# D1_2020-10-05_14-30-49.net
KiCad netlist of a schematic drawn in EasyEDA
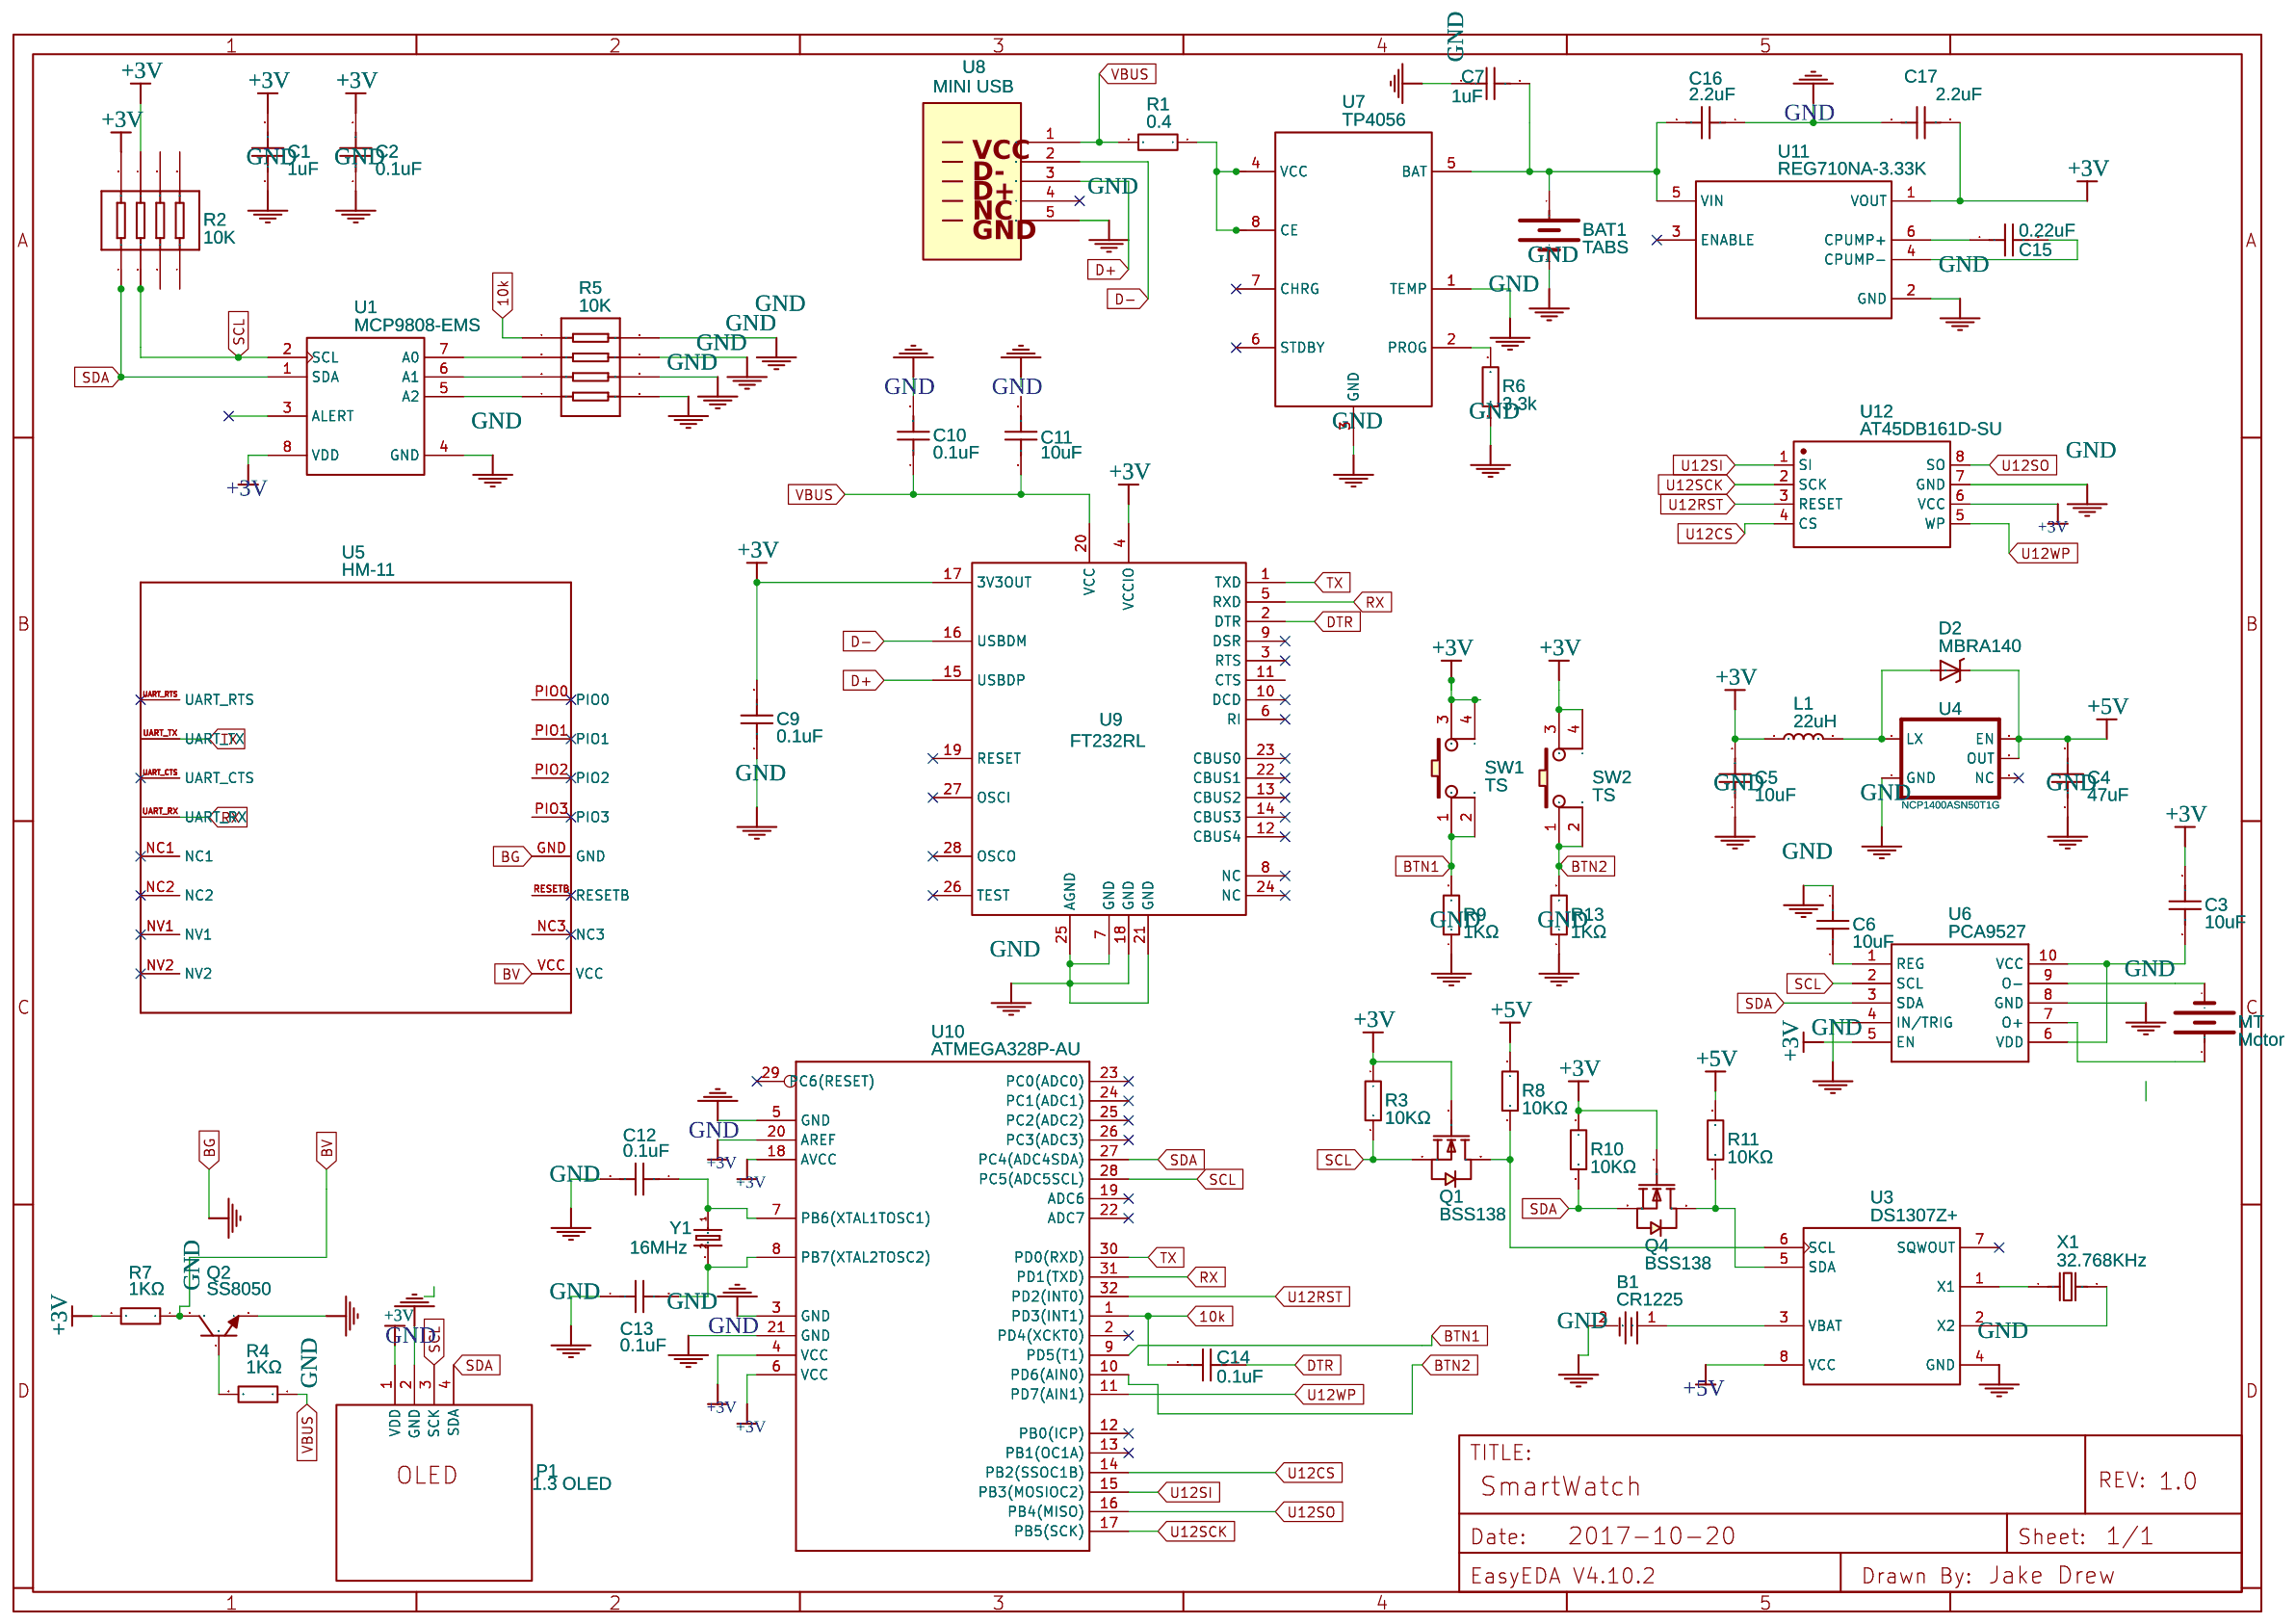
[diagram p0: schematic sheet]

(export (version "E")
  (design (tool "Eeschema 10.0.6"))
  (components
    (comp (ref "B1")
      (value "CR1225")
      (fields (field (name "BOM_Manufacturer Part") "CR1220-2"))
      (libsource (lib "") (part "Unknown_825_660"))
    )
    (comp (ref "BAT1")
      (value "TABS")
      (fields (field (name "BOM_Manufacturer Part") "?"))
      (libsource (lib "") (part "Unknown_785_100"))
    )
    (comp (ref "C1")
      (value "1uF")
      (fields
        (field (name "BOM_Manufacturer Part") "0805B105K250NT")
        (field (name "BOM_Supplier Part") "C89190")
      )
      (libsource (lib "") (part "Unknown_130_60"))
    )
    (comp (ref "C2")
      (value "0.1uF")
      (fields
        (field (name "BOM_Manufacturer Part") "0805B105K250NT")
        (field (name "BOM_Supplier Part") "C89190")
      )
      (libsource (lib "") (part "Unknown_175_60"))
    )
    (comp (ref "C3")
      (value "10uF")
      (fields
        (field (name "BOM_Manufacturer Part") "0805B105K250NT")
        (field (name "BOM_Supplier Part") "C89190")
      )
      (libsource (lib "") (part "Unknown_1110_445"))
    )
    (comp (ref "C4")
      (value "47uF")
      (fields
        (field (name "BOM_Manufacturer Part") "0805B105K250NT")
        (field (name "BOM_Supplier Part") "C89190")
      )
      (libsource (lib "") (part "Unknown_1050_380"))
    )
    (comp (ref "C5")
      (value "10uF")
      (fields
        (field (name "BOM_Manufacturer Part") "0805B105K250NT")
        (field (name "BOM_Supplier Part") "C89190")
      )
      (libsource (lib "") (part "Unknown_880_380"))
    )
    (comp (ref "C6")
      (value "10uF")
      (fields
        (field (name "BOM_Manufacturer Part") "0805B105K250NT")
        (field (name "BOM_Supplier Part") "C89190")
      )
      (libsource (lib "") (part "Unknown_930_455"))
    )
    (comp (ref "C7")
      (value "1uF")
      (fields
        (field (name "BOM_Manufacturer Part") "0805B105K250NT")
        (field (name "BOM_Supplier Part") "C89190")
      )
      (libsource (lib "") (part "Unknown_755_25"))
    )
    (comp (ref "C9")
      (value "0.1uF")
      (fields
        (field (name "BOM_Manufacturer Part") "0805B105K250NT")
        (field (name "BOM_Supplier Part") "C89190")
      )
      (libsource (lib "") (part "Unknown_380_350"))
    )
    (comp (ref "C10")
      (value "0.1uF")
      (fields
        (field (name "BOM_Manufacturer Part") "0805B105K250NT")
        (field (name "BOM_Supplier Part") "C89190")
      )
      (libsource (lib "") (part "Unknown_460_205"))
    )
    (comp (ref "C11")
      (value "10uF")
      (fields
        (field (name "BOM_Manufacturer Part") "0805B105K250NT")
        (field (name "BOM_Supplier Part") "C89190")
      )
      (libsource (lib "") (part "Unknown_515_205"))
    )
    (comp (ref "C12")
      (value "0.1uF")
      (fields
        (field (name "BOM_Manufacturer Part") "0805B105K250NT")
        (field (name "BOM_Supplier Part") "C89190")
      )
      (libsource (lib "") (part "Unknown_320_585"))
    )
    (comp (ref "C13")
      (value "0.1uF")
      (fields
        (field (name "BOM_Manufacturer Part") "0805B105K250NT")
        (field (name "BOM_Supplier Part") "C89190")
      )
      (libsource (lib "") (part "Unknown_320_645"))
    )
    (comp (ref "C14")
      (value "0.1uF")
      (fields
        (field (name "BOM_Manufacturer Part") "0805B105K250NT")
        (field (name "BOM_Supplier Part") "C89190")
      )
      (libsource (lib "") (part "Unknown_610_680"))
    )
    (comp (ref "C15")
      (value "0.22uF")
      (fields
        (field (name "BOM_Manufacturer Part") "0805B105K250NT")
        (field (name "BOM_Supplier Part") "C89190")
      )
      (libsource (lib "") (part "Unknown_1020_105"))
    )
    (comp (ref "C16")
      (value "2.2uF")
      (fields
        (field (name "BOM_Manufacturer Part") "0805B105K250NT")
        (field (name "BOM_Supplier Part") "C89190")
      )
      (libsource (lib "") (part "Unknown_865_45"))
    )
    (comp (ref "C17")
      (value "2.2uF")
      (fields
        (field (name "BOM_Manufacturer Part") "0805B105K250NT")
        (field (name "BOM_Supplier Part") "C89190")
      )
      (libsource (lib "") (part "Unknown_975_45"))
    )
    (comp (ref "D2")
      (value "MBRA140")
      (fields (field (name "BOM_Manufacturer Part") "?"))
      (libsource (lib "") (part "Unknown_990_325"))
    )
    (comp (ref "L1")
      (value "22uH")
      (fields (field (name "BOM_Manufacturer Part") "SDFL2012T220KTF"))
      (libsource (lib "") (part "Unknown_915_360"))
    )
    (comp (ref "MT")
      (value "Motor")
      (fields (field (name "BOM_Manufacturer Part") "?"))
      (libsource (lib "") (part "Unknown_1120_505"))
    )
    (comp (ref "P1")
      (value "1.3 OLED")
      (fields (field (name "BOM_Manufacturer Part") "?"))
      (libsource (lib "") (part "Unknown_245_790"))
    )
    (comp (ref "Q1")
      (value "BSS138")
      (fields (field (name "BOM_Supplier Part") "C78284"))
      (libsource (lib "") (part "Unknown_735_575"))
    )
    (comp (ref "Q2")
      (value "SS8050")
      (fields (field (name "BOM_Supplier Part") "C2150"))
      (libsource (lib "") (part "Unknown_105_665"))
    )
    (comp (ref "Q4")
      (value "BSS138")
      (fields (field (name "BOM_Supplier Part") "C78284"))
      (libsource (lib "") (part "Unknown_840_600"))
    )
    (comp (ref "R1")
      (value "0.4")
      (fields
        (field (name "BOM_Manufacturer Part") "0805W8F147KT5E")
        (field (name "BOM_Supplier Part") "C68930")
      )
      (libsource (lib "") (part "Unknown_585_55"))
    )
    (comp (ref "R2")
      (value "10K")
      (fields
        (field (name "BOM_Manufacturer Part") "4D03WGJ0102T5E")
        (field (name "BOM_Supplier Part") "C20197")
      )
      (libsource (lib "") (part "Unknown_70_95"))
    )
    (comp (ref "R3")
      (value "10KΩ")
      (fields
        (field (name "BOM_Manufacturer Part") "1206W4F1002T5E")
        (field (name "BOM_Supplier Part") "C17902")
      )
      (libsource (lib "") (part "Unknown_695_545"))
    )
    (comp (ref "R4")
      (value "1KΩ")
      (fields
        (field (name "BOM_Manufacturer Part") "1206W4F1001T5E")
        (field (name "BOM_Supplier Part") "C4410")
      )
      (libsource (lib "") (part "Unknown_125_695"))
    )
    (comp (ref "R5")
      (value "10K")
      (fields
        (field (name "BOM_Manufacturer Part") "4D03WGJ0102T5E")
        (field (name "BOM_Supplier Part") "C20197")
      )
      (libsource (lib "") (part "Unknown_295_170"))
    )
    (comp (ref "R6")
      (value "3.3k")
      (fields
        (field (name "BOM_Manufacturer Part") "1210W3F680KT5E")
        (field (name "BOM_Supplier Part") "C38887")
      )
      (libsource (lib "") (part "Unknown_755_180"))
    )
    (comp (ref "R7")
      (value "1KΩ")
      (fields
        (field (name "BOM_Manufacturer Part") "1206W4F1001T5E")
        (field (name "BOM_Supplier Part") "C4410")
      )
      (libsource (lib "") (part "Unknown_65_655"))
    )
    (comp (ref "R8")
      (value "10KΩ")
      (fields
        (field (name "BOM_Manufacturer Part") "1206W4F1002T5E")
        (field (name "BOM_Supplier Part") "C17902")
      )
      (libsource (lib "") (part "Unknown_765_540"))
    )
    (comp (ref "R9")
      (value "1KΩ")
      (fields
        (field (name "BOM_Manufacturer Part") "1206W4F1001T5E")
        (field (name "BOM_Supplier Part") "C4410")
      )
      (libsource (lib "") (part "Unknown_735_450"))
    )
    (comp (ref "R10")
      (value "10KΩ")
      (fields
        (field (name "BOM_Manufacturer Part") "1206W4F1002T5E")
        (field (name "BOM_Supplier Part") "C17902")
      )
      (libsource (lib "") (part "Unknown_800_570"))
    )
    (comp (ref "R11")
      (value "10KΩ")
      (fields
        (field (name "BOM_Manufacturer Part") "1206W4F1002T5E")
        (field (name "BOM_Supplier Part") "C17902")
      )
      (libsource (lib "") (part "Unknown_870_565"))
    )
    (comp (ref "R13")
      (value "1KΩ")
      (fields
        (field (name "BOM_Manufacturer Part") "1206W4F1001T5E")
        (field (name "BOM_Supplier Part") "C4410")
      )
      (libsource (lib "") (part "Unknown_790_450"))
    )
    (comp (ref "SW1")
      (value "TS")
      (fields
        (field (name "BOM_Manufacturer Part") "SWITCH-6x6x5_TH")
        (field (name "BOM_Supplier Part") "C69330")
      )
      (libsource (lib "") (part "Unknown_740_375"))
    )
    (comp (ref "SW2")
      (value "TS")
      (fields
        (field (name "BOM_Manufacturer Part") "SWITCH-6x6x5_TH")
        (field (name "BOM_Supplier Part") "C69330")
      )
      (libsource (lib "") (part "Unknown_795_380"))
    )
    (comp (ref "U1")
      (value "MCP9808-EMS")
      (fields (field (name "BOM_Manufacturer Part") "?"))
      (libsource (lib "") (part "Unknown_180_195"))
    )
    (comp (ref "U3")
      (value "DS1307Z+")
      (fields (field (name "BOM_Manufacturer Part") "DS1307Z+T&R") (field (name "BOM_Supplier Part") "C9868"))
      (libsource (lib "") (part "Unknown_955_650"))
    )
    (comp (ref "U4")
      (value "NCP1400ASN50T1G")
      (fields (field (name "BOM_Manufacturer Part") "?"))
      (libsource (lib "") (part "Unknown_995_370"))
    )
    (comp (ref "U5")
      (value "HM-11")
      (fields (field (name "BOM_Manufacturer Part") "?"))
      (libsource (lib "") (part "Unknown_185_390"))
    )
    (comp (ref "U6")
      (value "PCA9527")
      (fields (field (name "BOM_Manufacturer Part") "?"))
      (libsource (lib "") (part "Unknown_1000_495"))
    )
    (comp (ref "U7")
      (value "TP4056")
      (fields (field (name "BOM_Supplier Part") "C16581"))
      (libsource (lib "") (part "Unknown_685_130"))
    )
    (comp (ref "U8")
      (value "MINI USB")
      (fields (field (name "BOM_Manufacturer Part") "?"))
      (libsource (lib "") (part "Unknown_515_75"))
    )
    (comp (ref "U9")
      (value "FT232RL")
      (fields
        (field (name "BOM_Manufacturer Part") "FT232RL-REEL")
        (field (name "BOM_Supplier Part") "C8690")
      )
      (libsource (lib "") (part "Unknown_560_360"))
    )
    (comp (ref "U10") (value "ATMEGA328P-AU") (libsource (lib "") (part "Unknown_475_650")))
    (comp (ref "U11")
      (value "REG710NA-3.33K")
      (fields (field (name "BOM_Manufacturer Part") "?"))
      (libsource (lib "") (part "Unknown_910_115"))
    )
    (comp (ref "U12")
      (value "AT45DB161D-SU")
      (fields (field (name "BOM_Manufacturer Part") "?"))
      (libsource (lib "") (part "Unknown_950_210"))
    )
    (comp (ref "X1")
      (value "32.768KHz")
      (fields
        (field (name "BOM_Manufacturer Part") "DT-38 32.768KHz")
        (field (name "BOM_Supplier Part") "C93228")
      )
      (libsource (lib "") (part "Unknown_1050_640"))
    )
    (comp (ref "Y1")
      (value "16MHz")
      (fields (field (name "BOM_Manufacturer Part") "X053201602002"))
      (libsource (lib "") (part "Unknown_355_615"))
    )
  )
  (nets
    (net (code "1") (name "+3V") (class "Default")
      (node (ref "C1") (pin "2") (pinfunction "2_2") (pintype "unspecified"))
      (node (ref "C17") (pin "2") (pinfunction "2_2") (pintype "unspecified"))
      (node (ref "C2") (pin "2") (pinfunction "2_2") (pintype "unspecified"))
      (node (ref "C3") (pin "2") (pinfunction "2_2") (pintype "unspecified"))
      (node (ref "C5") (pin "2") (pinfunction "2_2") (pintype "unspecified"))
      (node (ref "C9") (pin "2") (pinfunction "2_2") (pintype "unspecified"))
      (node (ref "L1") (pin "1") (pinfunction "1_1") (pintype "unspecified"))
      (node (ref "P1") (pin "1") (pinfunction "VDD_1") (pintype "unspecified"))
      (node (ref "Q1") (pin "1") (pinfunction "G_1") (pintype "unspecified"))
      (node (ref "Q4") (pin "1") (pinfunction "G_1") (pintype "unspecified"))
      (node (ref "R10") (pin "1") (pinfunction "1_1") (pintype "input"))
      (node (ref "R2") (pin "7") (pinfunction "7_7") (pintype "input"))
      (node (ref "R2") (pin "8") (pinfunction "8_8") (pintype "input"))
      (node (ref "R3") (pin "1") (pinfunction "1_1") (pintype "input"))
      (node (ref "R7") (pin "2") (pinfunction "2_2") (pintype "input"))
      (node (ref "SW1") (pin "3") (pinfunction "3_3") (pintype "input"))
      (node (ref "SW1") (pin "4") (pinfunction "4_4") (pintype "input"))
      (node (ref "SW2") (pin "3") (pinfunction "3_3") (pintype "input"))
      (node (ref "SW2") (pin "4") (pinfunction "4_4") (pintype "input"))
      (node (ref "U1") (pin "8") (pinfunction "VDD_8") (pintype "passive"))
      (node (ref "U10") (pin "18") (pinfunction "AVCC_18") (pintype "unspecified"))
      (node (ref "U10") (pin "20") (pinfunction "AREF_20") (pintype "unspecified"))
      (node (ref "U10") (pin "4") (pinfunction "VCC_4") (pintype "unspecified"))
      (node (ref "U10") (pin "6") (pinfunction "VCC_6") (pintype "unspecified"))
      (node (ref "U11") (pin "1") (pinfunction "VOUT_1") (pintype "passive"))
      (node (ref "U12") (pin "6") (pinfunction "VCC_6") (pintype "unspecified"))
      (node (ref "U6") (pin "5") (pinfunction "EN_5") (pintype "unspecified"))
      (node (ref "U9") (pin "17") (pinfunction "3V3OUT_17") (pintype "output"))
      (node (ref "U9") (pin "4") (pinfunction "VCCIO_4") (pintype "passive"))
    )
    (net (code "2") (name "+5V") (class "Default")
      (node (ref "C4") (pin "2") (pinfunction "2_2") (pintype "unspecified"))
      (node (ref "D2") (pin "C") (pinfunction "C_C") (pintype "unspecified"))
      (node (ref "R11") (pin "2") (pinfunction "2_2") (pintype "input"))
      (node (ref "R8") (pin "2") (pinfunction "2_2") (pintype "input"))
      (node (ref "U3") (pin "8") (pinfunction "VCC_8") (pintype "passive"))
      (node (ref "U4") (pin "1") (pinfunction "EN_1") (pintype "input"))
      (node (ref "U4") (pin "2") (pinfunction "OUT_2") (pintype "unspecified"))
    )
    (net (code "3") (name "10k") (class "Default")
      (node (ref "C14") (pin "2") (pinfunction "2_2") (pintype "unspecified"))
      (node (ref "R5") (pin "1") (pinfunction "1_1") (pintype "input"))
      (node (ref "U10") (pin "1") (pinfunction "PD3(INT1)_1") (pintype "unspecified"))
    )
    (net (code "4") (name "BG") (class "Default")
      (node (ref "B1") (pin "2") (pinfunction "2_2") (pintype "input"))
      (node (ref "BAT1") (pin "-") (pinfunction "-_-") (pintype "passive"))
      (node (ref "C1") (pin "1") (pinfunction "1_1") (pintype "unspecified"))
      (node (ref "C10") (pin "2") (pinfunction "2_2") (pintype "unspecified"))
      (node (ref "C12") (pin "2") (pinfunction "2_2") (pintype "unspecified"))
      (node (ref "C13") (pin "1") (pinfunction "1_1") (pintype "unspecified"))
      (node (ref "C16") (pin "1") (pinfunction "1_1") (pintype "unspecified"))
      (node (ref "C17") (pin "1") (pinfunction "1_1") (pintype "unspecified"))
      (node (ref "C2") (pin "1") (pinfunction "1_1") (pintype "unspecified"))
      (node (ref "C4") (pin "1") (pinfunction "1_1") (pintype "unspecified"))
      (node (ref "C5") (pin "1") (pinfunction "1_1") (pintype "unspecified"))
      (node (ref "C6") (pin "2") (pinfunction "2_2") (pintype "unspecified"))
      (node (ref "C7") (pin "1") (pinfunction "1_1") (pintype "unspecified"))
      (node (ref "C9") (pin "1") (pinfunction "1_1") (pintype "unspecified"))
      (node (ref "P1") (pin "2") (pinfunction "GND_2") (pintype "unspecified"))
      (node (ref "Q2") (pin "2") (pinfunction "E_2") (pintype "unspecified"))
      (node (ref "R13") (pin "1") (pinfunction "1_1") (pintype "input"))
      (node (ref "R5") (pin "5") (pinfunction "5_5") (pintype "input"))
      (node (ref "R5") (pin "6") (pinfunction "6_6") (pintype "input"))
      (node (ref "R5") (pin "7") (pinfunction "7_7") (pintype "input"))
      (node (ref "R5") (pin "8") (pinfunction "8_8") (pintype "input"))
      (node (ref "R6") (pin "1") (pinfunction "1_1") (pintype "input"))
      (node (ref "R9") (pin "1") (pinfunction "1_1") (pintype "input"))
      (node (ref "U1") (pin "4") (pinfunction "GND_4") (pintype "passive"))
      (node (ref "U10") (pin "21") (pinfunction "GND_21") (pintype "unspecified"))
      (node (ref "U10") (pin "3") (pinfunction "GND_3") (pintype "unspecified"))
      (node (ref "U10") (pin "5") (pinfunction "GND_5") (pintype "unspecified"))
      (node (ref "U11") (pin "2") (pinfunction "GND_2") (pintype "passive"))
      (node (ref "U12") (pin "7") (pinfunction "GND_7") (pintype "unspecified"))
      (node (ref "U3") (pin "4") (pinfunction "GND_4") (pintype "passive"))
      (node (ref "U4") (pin "4") (pinfunction "GND_4") (pintype "input"))
      (node (ref "U5") (pin "GND") (pinfunction "GND_GND") (pintype "unspecified"))
      (node (ref "U6") (pin "4") (pinfunction "IN/TRIG_4") (pintype "unspecified"))
      (node (ref "U6") (pin "8") (pinfunction "GND_8") (pintype "unspecified"))
      (node (ref "U7") (pin "1") (pinfunction "TEMP_1") (pintype "unspecified"))
      (node (ref "U7") (pin "3") (pinfunction "GND_3") (pintype "unspecified"))
      (node (ref "U8") (pin "5") (pinfunction "5_5") (pintype "unspecified"))
      (node (ref "U9") (pin "18") (pinfunction "GND_18") (pintype "passive"))
      (node (ref "U9") (pin "21") (pinfunction "GND_21") (pintype "passive"))
      (node (ref "U9") (pin "25") (pinfunction "AGND_25") (pintype "passive"))
      (node (ref "U9") (pin "7") (pinfunction "GND_7") (pintype "passive"))
    )
    (net (code "5") (name "BTN1") (class "Default")
      (node (ref "R9") (pin "2") (pinfunction "2_2") (pintype "input"))
      (node (ref "SW1") (pin "1") (pinfunction "1_1") (pintype "input"))
      (node (ref "SW1") (pin "2") (pinfunction "2_2") (pintype "input"))
      (node (ref "U10") (pin "9") (pinfunction "PD5(T1)_9") (pintype "unspecified"))
    )
    (net (code "6") (name "BTN2") (class "Default")
      (node (ref "R13") (pin "2") (pinfunction "2_2") (pintype "input"))
      (node (ref "SW2") (pin "1") (pinfunction "1_1") (pintype "input"))
      (node (ref "SW2") (pin "2") (pinfunction "2_2") (pintype "input"))
      (node (ref "U10") (pin "10") (pinfunction "PD6(AIN0)_10") (pintype "unspecified"))
    )
    (net (code "7") (name "BV") (class "Default")
      (node (ref "Q2") (pin "3") (pinfunction "C_3") (pintype "unspecified"))
      (node (ref "R7") (pin "1") (pinfunction "1_1") (pintype "input"))
      (node (ref "U5") (pin "VCC") (pinfunction "VCC_VCC") (pintype "unspecified"))
    )
    (net (code "8") (name "D+") (class "Default")
      (node (ref "U8") (pin "3") (pinfunction "3_3") (pintype "unspecified"))
      (node (ref "U9") (pin "15") (pinfunction "USBDP_15") (pintype "bidirectional"))
    )
    (net (code "9") (name "D-") (class "Default")
      (node (ref "U8") (pin "2") (pinfunction "2_2") (pintype "unspecified"))
      (node (ref "U9") (pin "16") (pinfunction "USBDM_16") (pintype "bidirectional"))
    )
    (net (code "10") (name "DTR") (class "Default")
      (node (ref "C14") (pin "1") (pinfunction "1_1") (pintype "unspecified"))
      (node (ref "U9") (pin "2") (pinfunction "DTR_2") (pintype "output"))
    )
    (net (code "11") (name "Net-(Q1-D)") (class "Default")
      (node (ref "Q1") (pin "3") (pinfunction "D_3") (pintype "unspecified"))
      (node (ref "R8") (pin "1") (pinfunction "1_1") (pintype "input"))
      (node (ref "U3") (pin "6") (pinfunction "SCL_6") (pintype "unspecified"))
    )
    (net (code "12") (name "Net-(Q2-B)") (class "Default")
      (node (ref "Q2") (pin "1") (pinfunction "B_1") (pintype "unspecified"))
      (node (ref "R4") (pin "2") (pinfunction "2_2") (pintype "input"))
    )
    (net (code "13") (name "Net-(Q4-D)") (class "Default")
      (node (ref "Q4") (pin "3") (pinfunction "D_3") (pintype "unspecified"))
      (node (ref "R11") (pin "1") (pinfunction "1_1") (pintype "input"))
      (node (ref "U3") (pin "5") (pinfunction "SDA_5") (pintype "bidirectional"))
    )
    (net (code "14") (name "Net-(U1-A0)") (class "Default")
      (node (ref "R5") (pin "2") (pinfunction "2_2") (pintype "input"))
      (node (ref "U1") (pin "7") (pinfunction "A0_7") (pintype "unspecified"))
    )
    (net (code "15") (name "Net-(U1-A1)") (class "Default")
      (node (ref "R5") (pin "3") (pinfunction "3_3") (pintype "input"))
      (node (ref "U1") (pin "6") (pinfunction "A1_6") (pintype "unspecified"))
    )
    (net (code "16") (name "Net-(U1-A2)") (class "Default")
      (node (ref "R5") (pin "4") (pinfunction "4_4") (pintype "input"))
      (node (ref "U1") (pin "5") (pinfunction "A2_5") (pintype "unspecified"))
    )
    (net (code "17") (name "Net-(U3-VBAT)") (class "Default")
      (node (ref "B1") (pin "1") (pinfunction "1_1") (pintype "input"))
      (node (ref "U3") (pin "3") (pinfunction "VBAT_3") (pintype "passive"))
    )
    (net (code "18") (name "Net-(U3-X1)") (class "Default")
      (node (ref "U3") (pin "1") (pinfunction "X1_1") (pintype "unspecified"))
      (node (ref "X1") (pin "1") (pinfunction "1_1") (pintype "unspecified"))
    )
    (net (code "19") (name "Net-(U3-X2)") (class "Default")
      (node (ref "U3") (pin "2") (pinfunction "X2_2") (pintype "unspecified"))
      (node (ref "X1") (pin "2") (pinfunction "2_2") (pintype "unspecified"))
    )
    (net (code "20") (name "Net-(U4-LX)") (class "Default")
      (node (ref "D2") (pin "A") (pinfunction "A_A") (pintype "unspecified"))
      (node (ref "L1") (pin "2") (pinfunction "2_2") (pintype "unspecified"))
      (node (ref "U4") (pin "5") (pinfunction "LX_5") (pintype "input"))
    )
    (net (code "21") (name "Net-(U6-O+)") (class "Default")
      (node (ref "MT") (pin "+") (pinfunction "+_+") (pintype "passive"))
      (node (ref "U6") (pin "7") (pinfunction "O+_7") (pintype "unspecified"))
    )
    (net (code "22") (name "Net-(U6-O-)") (class "Default")
      (node (ref "MT") (pin "-") (pinfunction "-_-") (pintype "passive"))
      (node (ref "U6") (pin "9") (pinfunction "O-_9") (pintype "unspecified"))
    )
    (net (code "23") (name "Net-(U6-REG)") (class "Default")
      (node (ref "C6") (pin "1") (pinfunction "1_1") (pintype "unspecified"))
      (node (ref "U6") (pin "1") (pinfunction "REG_1") (pintype "unspecified"))
    )
    (net (code "24") (name "Net-(U6-VCC)") (class "Default")
      (node (ref "C3") (pin "1") (pinfunction "1_1") (pintype "unspecified"))
      (node (ref "U6") (pin "10") (pinfunction "VCC_10") (pintype "unspecified"))
      (node (ref "U6") (pin "6") (pinfunction "VDD_6") (pintype "unspecified"))
    )
    (net (code "25") (name "Net-(U7-CE)") (class "Default")
      (node (ref "R1") (pin "1") (pinfunction "1_1") (pintype "input"))
      (node (ref "U7") (pin "4") (pinfunction "VCC_4") (pintype "unspecified"))
      (node (ref "U7") (pin "8") (pinfunction "CE_8") (pintype "unspecified"))
    )
    (net (code "26") (name "Net-(U7-PROG)") (class "Default")
      (node (ref "R6") (pin "2") (pinfunction "2_2") (pintype "input"))
      (node (ref "U7") (pin "2") (pinfunction "PROG_2") (pintype "unspecified"))
    )
    (net (code "27") (name "Net-(U10-PB6(XTAL1TOSC1))") (class "Default")
      (node (ref "C12") (pin "1") (pinfunction "1_1") (pintype "unspecified"))
      (node (ref "U10") (pin "7") (pinfunction "PB6(XTAL1TOSC1)_7") (pintype "unspecified"))
      (node (ref "Y1") (pin "1") (pinfunction "1_1") (pintype "unspecified"))
    )
    (net (code "28") (name "Net-(U10-PB7(XTAL2TOSC2))") (class "Default")
      (node (ref "C13") (pin "2") (pinfunction "2_2") (pintype "unspecified"))
      (node (ref "U10") (pin "8") (pinfunction "PB7(XTAL2TOSC2)_8") (pintype "unspecified"))
      (node (ref "Y1") (pin "2") (pinfunction "2_2") (pintype "unspecified"))
    )
    (net (code "29") (name "Net-(U11-CPUMP+)") (class "Default")
      (node (ref "C15") (pin "1") (pinfunction "1_1") (pintype "unspecified"))
      (node (ref "U11") (pin "6") (pinfunction "CPUMP+_6") (pintype "unspecified"))
    )
    (net (code "30") (name "Net-(U11-CPUMP-)") (class "Default")
      (node (ref "C15") (pin "2") (pinfunction "2_2") (pintype "unspecified"))
      (node (ref "U11") (pin "4") (pinfunction "CPUMP-_4") (pintype "unspecified"))
    )
    (net (code "31") (name "Net-(U11-VIN)") (class "Default")
      (node (ref "BAT1") (pin "+") (pinfunction "+_+") (pintype "passive"))
      (node (ref "C16") (pin "2") (pinfunction "2_2") (pintype "unspecified"))
      (node (ref "C7") (pin "2") (pinfunction "2_2") (pintype "unspecified"))
      (node (ref "U11") (pin "5") (pinfunction "VIN_5") (pintype "passive"))
      (node (ref "U7") (pin "5") (pinfunction "BAT_5") (pintype "unspecified"))
    )
    (net (code "32") (name "RX") (class "Default")
      (node (ref "U10") (pin "31") (pinfunction "PD1(TXD)_31") (pintype "unspecified"))
      (node (ref "U5") (pin "UART_RX") (pinfunction "UART_RX_UART_RX") (pintype "unspecified"))
      (node (ref "U9") (pin "5") (pinfunction "RXD_5") (pintype "unspecified"))
    )
    (net (code "33") (name "SCL") (class "Default")
      (node (ref "P1") (pin "3") (pinfunction "SCK_3") (pintype "unspecified"))
      (node (ref "Q1") (pin "2") (pinfunction "S_2") (pintype "unspecified"))
      (node (ref "R2") (pin "2") (pinfunction "2_2") (pintype "input"))
      (node (ref "R3") (pin "2") (pinfunction "2_2") (pintype "input"))
      (node (ref "U1") (pin "2") (pinfunction "SCL_2") (pintype "unspecified"))
      (node (ref "U10") (pin "28") (pinfunction "PC5(ADC5SCL)_28") (pintype "unspecified"))
      (node (ref "U6") (pin "2") (pinfunction "SCL_2") (pintype "unspecified"))
    )
    (net (code "34") (name "SDA") (class "Default")
      (node (ref "P1") (pin "4") (pinfunction "SDA_4") (pintype "unspecified"))
      (node (ref "Q4") (pin "2") (pinfunction "S_2") (pintype "unspecified"))
      (node (ref "R10") (pin "2") (pinfunction "2_2") (pintype "input"))
      (node (ref "R2") (pin "1") (pinfunction "1_1") (pintype "input"))
      (node (ref "U1") (pin "1") (pinfunction "SDA_1") (pintype "bidirectional"))
      (node (ref "U10") (pin "27") (pinfunction "PC4(ADC4SDA)_27") (pintype "unspecified"))
      (node (ref "U6") (pin "3") (pinfunction "SDA_3") (pintype "unspecified"))
    )
    (net (code "35") (name "TX") (class "Default")
      (node (ref "U10") (pin "30") (pinfunction "PD0(RXD)_30") (pintype "unspecified"))
      (node (ref "U5") (pin "UART_TX") (pinfunction "UART_TX_UART_TX") (pintype "unspecified"))
      (node (ref "U9") (pin "1") (pinfunction "TXD_1") (pintype "output"))
    )
    (net (code "36") (name "U12CS") (class "Default")
      (node (ref "U10") (pin "14") (pinfunction "PB2(SSOC1B)_14") (pintype "unspecified"))
      (node (ref "U12") (pin "4") (pinfunction "CS_4") (pintype "unspecified"))
    )
    (net (code "37") (name "U12RST") (class "Default")
      (node (ref "U10") (pin "32") (pinfunction "PD2(INT0)_32") (pintype "unspecified"))
      (node (ref "U12") (pin "3") (pinfunction "RESET_3") (pintype "unspecified"))
    )
    (net (code "38") (name "U12SCK") (class "Default")
      (node (ref "U10") (pin "17") (pinfunction "PB5(SCK)_17") (pintype "unspecified"))
      (node (ref "U12") (pin "2") (pinfunction "SCK_2") (pintype "unspecified"))
    )
    (net (code "39") (name "U12SI") (class "Default")
      (node (ref "U10") (pin "15") (pinfunction "PB3(MOSIOC2)_15") (pintype "unspecified"))
      (node (ref "U12") (pin "1") (pinfunction "SI_1") (pintype "unspecified"))
    )
    (net (code "40") (name "U12SO") (class "Default")
      (node (ref "U10") (pin "16") (pinfunction "PB4(MISO)_16") (pintype "unspecified"))
      (node (ref "U12") (pin "8") (pinfunction "SO_8") (pintype "unspecified"))
    )
    (net (code "41") (name "U12WP") (class "Default")
      (node (ref "U10") (pin "11") (pinfunction "PD7(AIN1)_11") (pintype "unspecified"))
      (node (ref "U12") (pin "5") (pinfunction "WP_5") (pintype "unspecified"))
    )
    (net (code "42") (name "VBUS") (class "Default")
      (node (ref "C10") (pin "1") (pinfunction "1_1") (pintype "unspecified"))
      (node (ref "C11") (pin "1") (pinfunction "1_1") (pintype "unspecified"))
      (node (ref "R1") (pin "2") (pinfunction "2_2") (pintype "input"))
      (node (ref "R4") (pin "1") (pinfunction "1_1") (pintype "input"))
      (node (ref "U8") (pin "1") (pinfunction "1_1") (pintype "unspecified"))
      (node (ref "U9") (pin "20") (pinfunction "VCC_20") (pintype "passive"))
    )
    (net (code "43") (name "unconnected-(C11-Pad2)") (class "Default")
      (node (ref "C11") (pin "2") (pinfunction "2_2") (pintype "unspecified"))
    )
    (net (code "44") (name "unconnected-(R2-Pad3)") (class "Default")
      (node (ref "R2") (pin "3") (pinfunction "3_3") (pintype "input"))
    )
    (net (code "45") (name "unconnected-(R2-Pad4)") (class "Default")
      (node (ref "R2") (pin "4") (pinfunction "4_4") (pintype "input"))
    )
    (net (code "46") (name "unconnected-(R2-Pad5)") (class "Default")
      (node (ref "R2") (pin "5") (pinfunction "5_5") (pintype "input"))
    )
    (net (code "47") (name "unconnected-(R2-Pad6)") (class "Default")
      (node (ref "R2") (pin "6") (pinfunction "6_6") (pintype "input"))
    )
    (net (code "48") (name "unconnected-(U1-ALERT-Pad3)") (class "Default")
      (node (ref "U1") (pin "3") (pinfunction "ALERT_3") (pintype "unspecified+no_connect"))
    )
    (net (code "49") (name "unconnected-(U3-SQWOUT-Pad7)") (class "Default")
      (node (ref "U3") (pin "7") (pinfunction "SQWOUT_7") (pintype "unspecified+no_connect"))
    )
    (net (code "50") (name "unconnected-(U4-NC-Pad3)") (class "Default")
      (node (ref "U4") (pin "3") (pinfunction "NC_3") (pintype "input+no_connect"))
    )
    (net (code "51") (name "unconnected-(U5-PadNC1)") (class "Default")
      (node (ref "U5") (pin "NC1") (pinfunction "NC1_NC1") (pintype "unspecified+no_connect"))
    )
    (net (code "52") (name "unconnected-(U5-PadNC2)") (class "Default")
      (node (ref "U5") (pin "NC2") (pinfunction "NC2_NC2") (pintype "unspecified+no_connect"))
    )
    (net (code "53") (name "unconnected-(U5-PadNC3)") (class "Default")
      (node (ref "U5") (pin "NC3") (pinfunction "NC3_NC3") (pintype "unspecified"))
    )
    (net (code "54") (name "unconnected-(U5-PadNV1)") (class "Default")
      (node (ref "U5") (pin "NV1") (pinfunction "NV1_NV1") (pintype "unspecified+no_connect"))
    )
    (net (code "55") (name "unconnected-(U5-PadNV2)") (class "Default")
      (node (ref "U5") (pin "NV2") (pinfunction "NV2_NV2") (pintype "unspecified+no_connect"))
    )
    (net (code "56") (name "unconnected-(U5-PadPIO0)") (class "Default")
      (node (ref "U5") (pin "PIO0") (pinfunction "PIO0_PIO0") (pintype "unspecified"))
    )
    (net (code "57") (name "unconnected-(U5-PadPIO1)") (class "Default")
      (node (ref "U5") (pin "PIO1") (pinfunction "PIO1_PIO1") (pintype "unspecified"))
    )
    (net (code "58") (name "unconnected-(U5-PadPIO2)") (class "Default")
      (node (ref "U5") (pin "PIO2") (pinfunction "PIO2_PIO2") (pintype "unspecified"))
    )
    (net (code "59") (name "unconnected-(U5-PadPIO3)") (class "Default")
      (node (ref "U5") (pin "PIO3") (pinfunction "PIO3_PIO3") (pintype "unspecified"))
    )
    (net (code "60") (name "unconnected-(U5-PadRESETB)") (class "Default")
      (node (ref "U5") (pin "RESETB") (pinfunction "RESETB_RESETB") (pintype "unspecified"))
    )
    (net (code "61") (name "unconnected-(U5-PadUART_CTS)") (class "Default")
      (node (ref "U5") (pin "UART_CTS") (pinfunction "UART_CTS_UART_CTS") (pintype "unspecified+no_connect"))
    )
    (net (code "62") (name "unconnected-(U5-PadUART_RTS)") (class "Default")
      (node (ref "U5") (pin "UART_RTS") (pinfunction "UART_RTS_UART_RTS") (pintype "unspecified+no_connect"))
    )
    (net (code "63") (name "unconnected-(U7-CHRG-Pad7)") (class "Default")
      (node (ref "U7") (pin "7") (pinfunction "CHRG_7") (pintype "unspecified+no_connect"))
    )
    (net (code "64") (name "unconnected-(U7-STDBY-Pad6)") (class "Default")
      (node (ref "U7") (pin "6") (pinfunction "STDBY_6") (pintype "unspecified+no_connect"))
    )
    (net (code "65") (name "unconnected-(U8-Pad4)") (class "Default")
      (node (ref "U8") (pin "4") (pinfunction "4_4") (pintype "unspecified+no_connect"))
    )
    (net (code "66") (name "unconnected-(U9-CBUS0-Pad23)") (class "Default")
      (node (ref "U9") (pin "23") (pinfunction "CBUS0_23") (pintype "bidirectional+no_connect"))
    )
    (net (code "67") (name "unconnected-(U9-CBUS1-Pad22)") (class "Default")
      (node (ref "U9") (pin "22") (pinfunction "CBUS1_22") (pintype "bidirectional+no_connect"))
    )
    (net (code "68") (name "unconnected-(U9-CBUS2-Pad13)") (class "Default")
      (node (ref "U9") (pin "13") (pinfunction "CBUS2_13") (pintype "bidirectional+no_connect"))
    )
    (net (code "69") (name "unconnected-(U9-CBUS3-Pad14)") (class "Default")
      (node (ref "U9") (pin "14") (pinfunction "CBUS3_14") (pintype "bidirectional+no_connect"))
    )
    (net (code "70") (name "unconnected-(U9-CBUS4-Pad12)") (class "Default")
      (node (ref "U9") (pin "12") (pinfunction "CBUS4_12") (pintype "bidirectional+no_connect"))
    )
    (net (code "71") (name "unconnected-(U9-CTS-Pad11)") (class "Default")
      (node (ref "U9") (pin "11") (pinfunction "CTS_11") (pintype "unspecified"))
    )
    (net (code "72") (name "unconnected-(U9-DCD-Pad10)") (class "Default")
      (node (ref "U9") (pin "10") (pinfunction "DCD_10") (pintype "unspecified+no_connect"))
    )
    (net (code "73") (name "unconnected-(U9-DSR-Pad9)") (class "Default")
      (node (ref "U9") (pin "9") (pinfunction "DSR_9") (pintype "unspecified+no_connect"))
    )
    (net (code "74") (name "unconnected-(U9-NC-Pad8)") (class "Default")
      (node (ref "U9") (pin "8") (pinfunction "NC_8") (pintype "unspecified+no_connect"))
    )
    (net (code "75") (name "unconnected-(U9-NC-Pad24)") (class "Default")
      (node (ref "U9") (pin "24") (pinfunction "NC_24") (pintype "unspecified+no_connect"))
    )
    (net (code "76") (name "unconnected-(U9-OSCI-Pad27)") (class "Default")
      (node (ref "U9") (pin "27") (pinfunction "OSCI_27") (pintype "unspecified+no_connect"))
    )
    (net (code "77") (name "unconnected-(U9-OSCO-Pad28)") (class "Default")
      (node (ref "U9") (pin "28") (pinfunction "OSCO_28") (pintype "output+no_connect"))
    )
    (net (code "78") (name "unconnected-(U9-RESET-Pad19)") (class "Default")
      (node (ref "U9") (pin "19") (pinfunction "RESET_19") (pintype "unspecified+no_connect"))
    )
    (net (code "79") (name "unconnected-(U9-RI-Pad6)") (class "Default")
      (node (ref "U9") (pin "6") (pinfunction "RI_6") (pintype "unspecified+no_connect"))
    )
    (net (code "80") (name "unconnected-(U9-RTS-Pad3)") (class "Default")
      (node (ref "U9") (pin "3") (pinfunction "RTS_3") (pintype "output+no_connect"))
    )
    (net (code "81") (name "unconnected-(U9-TEST-Pad26)") (class "Default")
      (node (ref "U9") (pin "26") (pinfunction "TEST_26") (pintype "unspecified+no_connect"))
    )
    (net (code "82") (name "unconnected-(U10-ADC6-Pad19)") (class "Default")
      (node (ref "U10") (pin "19") (pinfunction "ADC6_19") (pintype "unspecified+no_connect"))
    )
    (net (code "83") (name "unconnected-(U10-ADC7-Pad22)") (class "Default")
      (node (ref "U10") (pin "22") (pinfunction "ADC7_22") (pintype "unspecified+no_connect"))
    )
    (net (code "84") (name "unconnected-(U10-PB0(ICP)-Pad12)") (class "Default")
      (node (ref "U10") (pin "12") (pinfunction "PB0(ICP)_12") (pintype "unspecified+no_connect"))
    )
    (net (code "85") (name "unconnected-(U10-PB1(OC1A)-Pad13)") (class "Default")
      (node (ref "U10") (pin "13") (pinfunction "PB1(OC1A)_13") (pintype "unspecified+no_connect"))
    )
    (net (code "86") (name "unconnected-(U10-PC0(ADC0)-Pad23)") (class "Default")
      (node (ref "U10") (pin "23") (pinfunction "PC0(ADC0)_23") (pintype "unspecified+no_connect"))
    )
    (net (code "87") (name "unconnected-(U10-PC1(ADC1)-Pad24)") (class "Default")
      (node (ref "U10") (pin "24") (pinfunction "PC1(ADC1)_24") (pintype "unspecified+no_connect"))
    )
    (net (code "88") (name "unconnected-(U10-PC2(ADC2)-Pad25)") (class "Default")
      (node (ref "U10") (pin "25") (pinfunction "PC2(ADC2)_25") (pintype "unspecified+no_connect"))
    )
    (net (code "89") (name "unconnected-(U10-PC3(ADC3)-Pad26)") (class "Default")
      (node (ref "U10") (pin "26") (pinfunction "PC3(ADC3)_26") (pintype "unspecified+no_connect"))
    )
    (net (code "90") (name "unconnected-(U10-PC6(RESET)-Pad29)") (class "Default")
      (node (ref "U10") (pin "29") (pinfunction "PC6(RESET)_29") (pintype "unspecified+no_connect"))
    )
    (net (code "91") (name "unconnected-(U10-PD4(XCKT0)-Pad2)") (class "Default")
      (node (ref "U10") (pin "2") (pinfunction "PD4(XCKT0)_2") (pintype "unspecified+no_connect"))
    )
    (net (code "92") (name "unconnected-(U11-ENABLE-Pad3)") (class "Default")
      (node (ref "U11") (pin "3") (pinfunction "ENABLE_3") (pintype "unspecified+no_connect"))
    )
  )
)
